# Arduino-Mini-v5.net
KiCad netlist of a schematic drawn in EAGLE
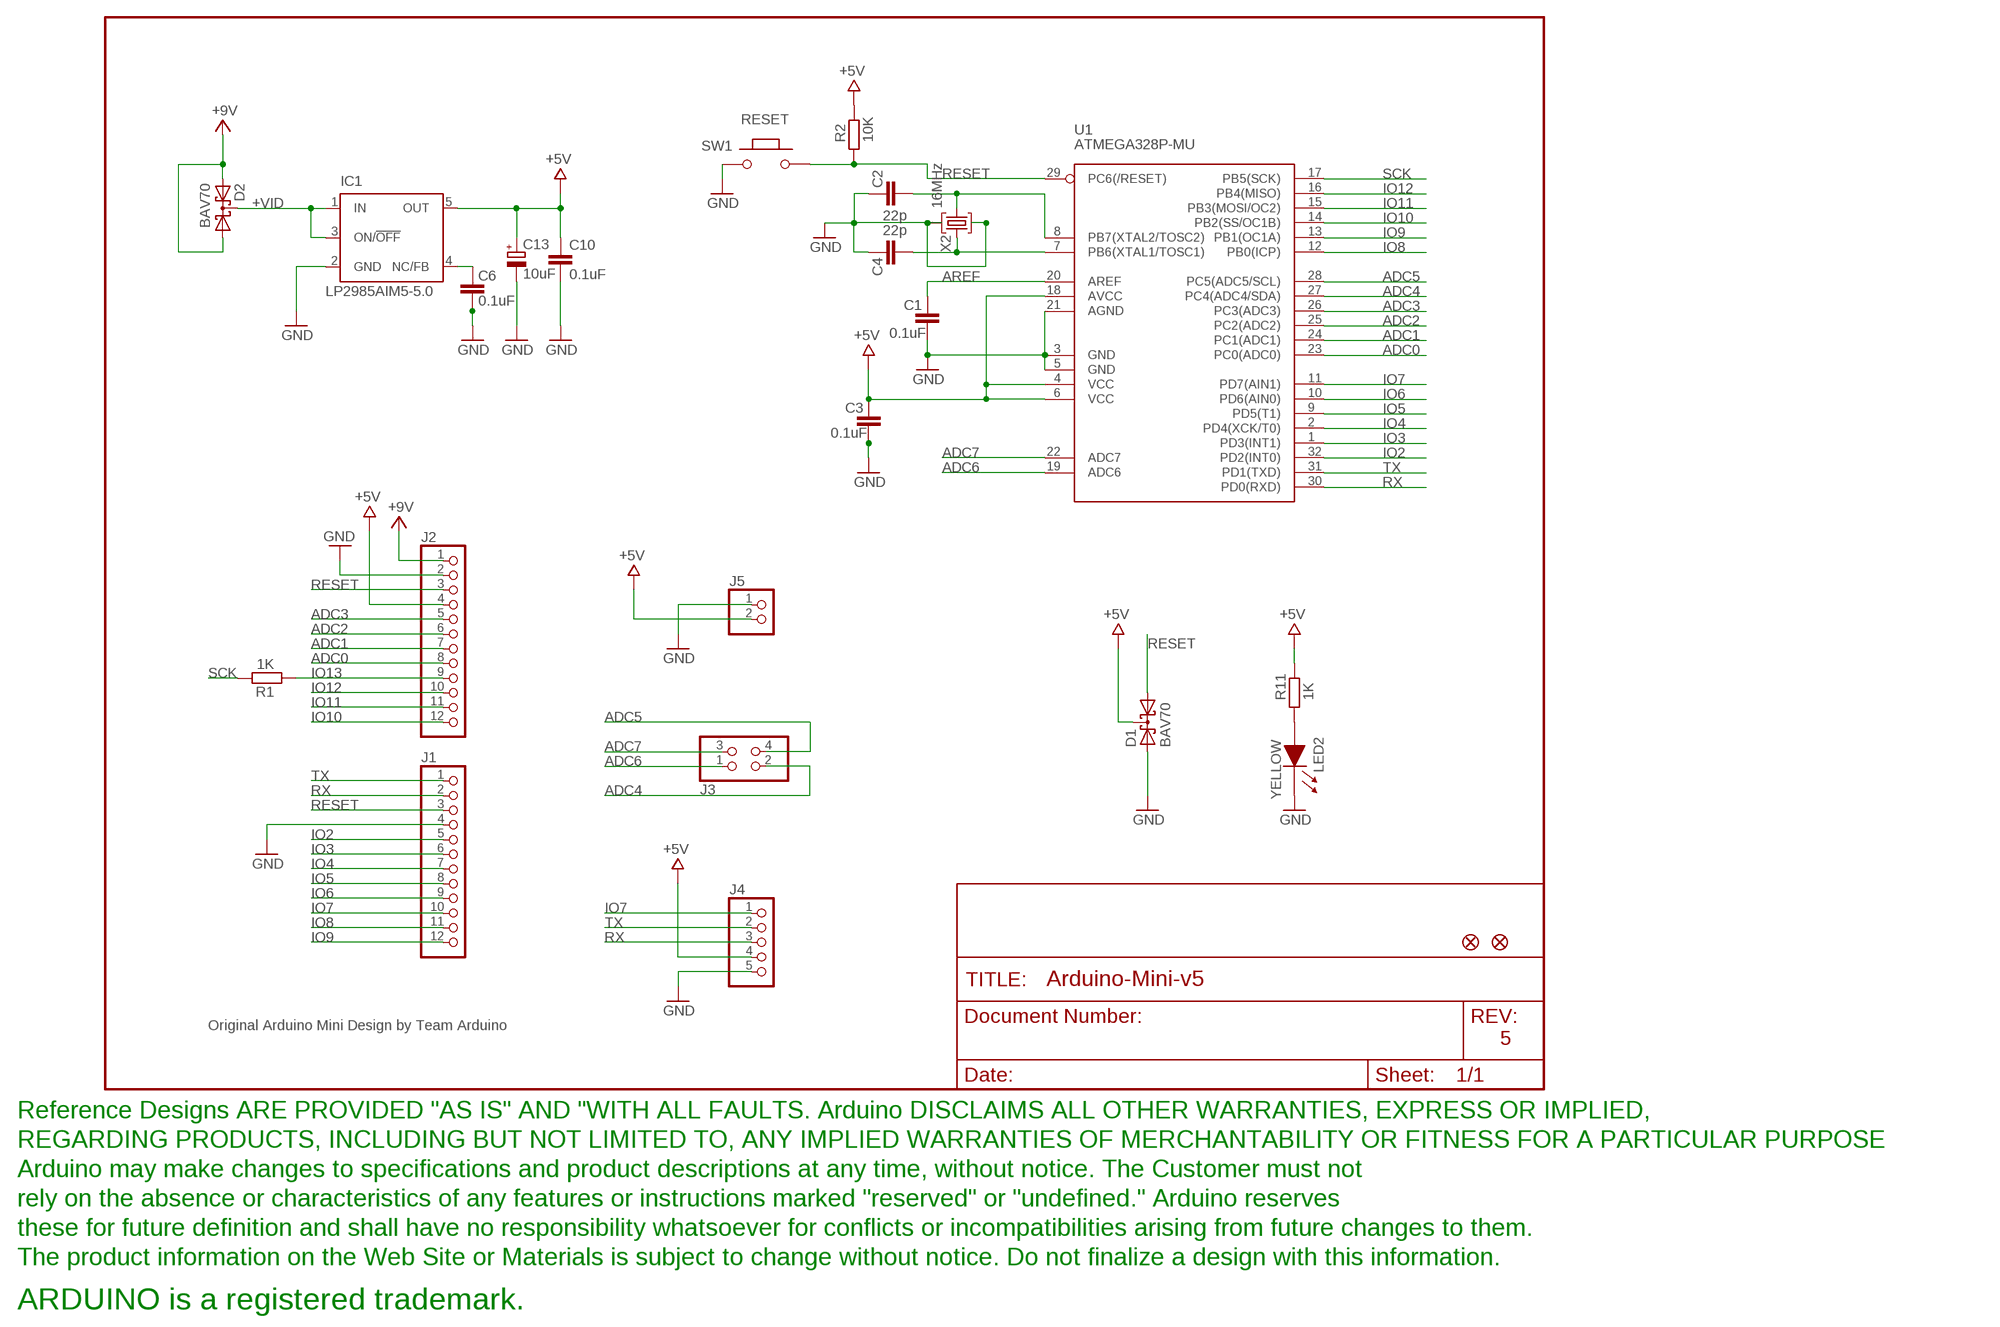
[diagram p0: schematic, sheet 1]

(export (version "E")
  (design (tool "Eeschema 10.0.6"))
  (components
    (comp (ref "C1")
      (value "0.1uF")
      (footprint "eagle-import:C0603-ROUND")
      (libsource (lib "eagle-import") (part "C-EUC0603"))
    )
    (comp (ref "C2")
      (value "22p")
      (footprint "eagle-import:C0603-ROUND")
      (libsource (lib "eagle-import") (part "C-EUC0603"))
    )
    (comp (ref "C3")
      (value "0.1uF")
      (footprint "eagle-import:C0603-ROUND")
      (libsource (lib "eagle-import") (part "C-EUC0603"))
    )
    (comp (ref "C4")
      (value "22p")
      (footprint "eagle-import:C0603-ROUND")
      (libsource (lib "eagle-import") (part "C-EUC0603"))
    )
    (comp (ref "C6")
      (value "0.1uF")
      (footprint "eagle-import:C0603-ROUND")
      (libsource (lib "eagle-import") (part "C-EUC0603"))
    )
    (comp (ref "C10")
      (value "0.1uF")
      (footprint "eagle-import:C0603-ROUND")
      (libsource (lib "eagle-import") (part "C-EUC0603"))
    )
    (comp (ref "C13")
      (value "10uF")
      (footprint "eagle-import:SMC_B")
      (libsource (lib "eagle-import") (part "CPOL-EUSMCB"))
    )
    (comp (ref "D1")
      (value "BAV70")
      (footprint "eagle-import:SOT23")
      (libsource (lib "eagle-import") (part "BAS70-05"))
    )
    (comp (ref "D2")
      (value "BAV70")
      (footprint "eagle-import:SOT23")
      (libsource (lib "eagle-import") (part "BAS70-05"))
    )
    (comp (ref "IC1")
      (value "LP2985AIM5-5.0")
      (footprint "eagle-import:SOT23-DBV")
      (libsource (lib "eagle-import") (part "LP2985-XXDBVR50"))
    )
    (comp (ref "J1")
      (value "PINHD-1X12")
      (footprint "eagle-import:1X12")
      (libsource (lib "eagle-import") (part "PINHD-1X12"))
    )
    (comp (ref "J2")
      (value "PINHD-1X12")
      (footprint "eagle-import:1X12")
      (libsource (lib "eagle-import") (part "PINHD-1X12"))
    )
    (comp (ref "J3")
      (value "PINHD-2X2")
      (footprint "eagle-import:2X02")
      (libsource (lib "eagle-import") (part "PINHD-2X2"))
    )
    (comp (ref "J4")
      (value "PINHD-1X5")
      (footprint "eagle-import:1X5")
      (libsource (lib "eagle-import") (part "PINHD-1X5"))
    )
    (comp (ref "J5")
      (value "PINHD-1X2")
      (footprint "eagle-import:1X2")
      (libsource (lib "eagle-import") (part "PINHD-1X2"))
    )
    (comp (ref "LED2")
      (value "YELLOW")
      (footprint "eagle-import:SMD_LED0805")
      (libsource (lib "eagle-import") (part "MYSMD_LED0805"))
    )
    (comp (ref "R1")
      (value "1K")
      (footprint "eagle-import:R0603-ROUND")
      (libsource (lib "eagle-import") (part "R-EU_R0603"))
    )
    (comp (ref "R2")
      (value "10K")
      (footprint "eagle-import:R0603-ROUND")
      (libsource (lib "eagle-import") (part "R-EU_R0603"))
    )
    (comp (ref "R11")
      (value "1K")
      (footprint "eagle-import:R0603-ROUND")
      (libsource (lib "eagle-import") (part "R-EU_R0603"))
    )
    (comp (ref "SW1")
      (value "RESET")
      (footprint "eagle-import:SMD_157SW")
      (libsource (lib "eagle-import") (part "MYSMD_PB157"))
    )
    (comp (ref "U$2")
      (value "FIDUCIAL1X2")
      (footprint "eagle-import:FIDUCIAL-1X2")
      (libsource (lib "eagle-import") (part "FIDUCIAL1X2"))
    )
    (comp (ref "U$4")
      (value "FIDUCIAL1X2")
      (footprint "eagle-import:FIDUCIAL-1X2")
      (libsource (lib "eagle-import") (part "FIDUCIAL1X2"))
    )
    (comp (ref "U$11")
      (value "DISCLAIMER")
      (footprint "eagle-import:DISCLAIMER")
      (libsource (lib "eagle-import") (part "DISCLAIMER"))
    )
    (comp (ref "U1")
      (value "ATMEGA328P-MU")
      (footprint "eagle-import:MLF32-M1-A")
      (libsource (lib "eagle-import") (part "ATMEGAXX8-MU"))
    )
    (comp (ref "X2")
      (value "16MHz")
      (footprint "eagle-import:CRYSTAL-3.2-2.5")
      (libsource (lib "eagle-import") (part "CRYSTAL-3.2-2.5"))
    )
  )
  (nets
    (net (code "1") (name "+5V") (class "Default")
      (node (ref "C10") (pin "1") (pinfunction "1_1") (pintype "passive"))
      (node (ref "C13") (pin "+") (pinfunction "+_+") (pintype "passive"))
      (node (ref "C3") (pin "2") (pinfunction "2_2") (pintype "passive"))
      (node (ref "D1") (pin "3") (pinfunction "C_3") (pintype "passive"))
      (node (ref "IC1") (pin "5") (pinfunction "OUT_5") (pintype "passive"))
      (node (ref "J2") (pin "4") (pinfunction "4_4") (pintype "passive"))
      (node (ref "J4") (pin "4") (pinfunction "4_4") (pintype "passive"))
      (node (ref "J5") (pin "2") (pinfunction "2_2") (pintype "passive"))
      (node (ref "R11") (pin "2") (pinfunction "2_2") (pintype "passive"))
      (node (ref "R2") (pin "2") (pinfunction "2_2") (pintype "passive"))
      (node (ref "U1") (pin "18") (pinfunction "AVCC_18") (pintype "bidirectional"))
      (node (ref "U1") (pin "4") (pinfunction "VCC_4") (pintype "bidirectional"))
      (node (ref "U1") (pin "6") (pinfunction "VCC_6") (pintype "bidirectional"))
    )
    (net (code "2") (name "+9V") (class "Default")
      (node (ref "D2") (pin "1") (pinfunction "A1_1") (pintype "passive"))
      (node (ref "D2") (pin "2") (pinfunction "A2_2") (pintype "passive"))
      (node (ref "J2") (pin "1") (pinfunction "1_1") (pintype "passive"))
    )
    (net (code "3") (name "/+VID") (class "Default")
      (node (ref "D2") (pin "3") (pinfunction "C_3") (pintype "passive"))
      (node (ref "IC1") (pin "1") (pinfunction "IN_1") (pintype "input"))
      (node (ref "IC1") (pin "3") (pinfunction "ON/~{OFF}_3") (pintype "input"))
    )
    (net (code "4") (name "/ADC0") (class "Default")
      (node (ref "J2") (pin "8") (pinfunction "8_8") (pintype "passive"))
      (node (ref "U1") (pin "23") (pinfunction "PC0(ADC0)_23") (pintype "bidirectional"))
    )
    (net (code "5") (name "/ADC1") (class "Default")
      (node (ref "J2") (pin "7") (pinfunction "7_7") (pintype "passive"))
      (node (ref "U1") (pin "24") (pinfunction "PC1(ADC1)_24") (pintype "bidirectional"))
    )
    (net (code "6") (name "/ADC2") (class "Default")
      (node (ref "J2") (pin "6") (pinfunction "6_6") (pintype "passive"))
      (node (ref "U1") (pin "25") (pinfunction "PC2(ADC2)_25") (pintype "bidirectional"))
    )
    (net (code "7") (name "/ADC3") (class "Default")
      (node (ref "J2") (pin "5") (pinfunction "5_5") (pintype "passive"))
      (node (ref "U1") (pin "26") (pinfunction "PC3(ADC3)_26") (pintype "bidirectional"))
    )
    (net (code "8") (name "/ADC4") (class "Default")
      (node (ref "J3") (pin "2") (pinfunction "2_2") (pintype "passive"))
      (node (ref "U1") (pin "27") (pinfunction "PC4(ADC4/SDA)_27") (pintype "bidirectional"))
    )
    (net (code "9") (name "/ADC5") (class "Default")
      (node (ref "J3") (pin "4") (pinfunction "4_4") (pintype "passive"))
      (node (ref "U1") (pin "28") (pinfunction "PC5(ADC5/SCL)_28") (pintype "bidirectional"))
    )
    (net (code "10") (name "/ADC6") (class "Default")
      (node (ref "J3") (pin "1") (pinfunction "1_1") (pintype "passive"))
      (node (ref "U1") (pin "19") (pinfunction "ADC6_19") (pintype "bidirectional"))
    )
    (net (code "11") (name "/ADC7") (class "Default")
      (node (ref "J3") (pin "3") (pinfunction "3_3") (pintype "passive"))
      (node (ref "U1") (pin "22") (pinfunction "ADC7_22") (pintype "bidirectional"))
    )
    (net (code "12") (name "/AREF") (class "Default")
      (node (ref "C1") (pin "2") (pinfunction "2_2") (pintype "passive"))
      (node (ref "U1") (pin "20") (pinfunction "AREF_20") (pintype "bidirectional"))
    )
    (net (code "13") (name "/IO2") (class "Default")
      (node (ref "J1") (pin "5") (pinfunction "5_5") (pintype "passive"))
      (node (ref "U1") (pin "32") (pinfunction "PD2(INT0)_32") (pintype "bidirectional"))
    )
    (net (code "14") (name "/IO3") (class "Default")
      (node (ref "J1") (pin "6") (pinfunction "6_6") (pintype "passive"))
      (node (ref "U1") (pin "1") (pinfunction "PD3(INT1)_1") (pintype "bidirectional"))
    )
    (net (code "15") (name "/IO4") (class "Default")
      (node (ref "J1") (pin "7") (pinfunction "7_7") (pintype "passive"))
      (node (ref "U1") (pin "2") (pinfunction "PD4(XCK/T0)_2") (pintype "bidirectional"))
    )
    (net (code "16") (name "/IO5") (class "Default")
      (node (ref "J1") (pin "8") (pinfunction "8_8") (pintype "passive"))
      (node (ref "U1") (pin "9") (pinfunction "PD5(T1)_9") (pintype "bidirectional"))
    )
    (net (code "17") (name "/IO6") (class "Default")
      (node (ref "J1") (pin "9") (pinfunction "9_9") (pintype "passive"))
      (node (ref "U1") (pin "10") (pinfunction "PD6(AIN0)_10") (pintype "bidirectional"))
    )
    (net (code "18") (name "/IO7") (class "Default")
      (node (ref "J1") (pin "10") (pinfunction "10_10") (pintype "passive"))
      (node (ref "J4") (pin "1") (pinfunction "1_1") (pintype "passive"))
      (node (ref "U1") (pin "11") (pinfunction "PD7(AIN1)_11") (pintype "bidirectional"))
    )
    (net (code "19") (name "/IO8") (class "Default")
      (node (ref "J1") (pin "11") (pinfunction "11_11") (pintype "passive"))
      (node (ref "U1") (pin "12") (pinfunction "PB0(ICP)_12") (pintype "bidirectional"))
    )
    (net (code "20") (name "/IO9") (class "Default")
      (node (ref "J1") (pin "12") (pinfunction "12_12") (pintype "passive"))
      (node (ref "U1") (pin "13") (pinfunction "PB1(OC1A)_13") (pintype "bidirectional"))
    )
    (net (code "21") (name "/IO10") (class "Default")
      (node (ref "J2") (pin "12") (pinfunction "12_12") (pintype "passive"))
      (node (ref "U1") (pin "14") (pinfunction "PB2(SS/OC1B)_14") (pintype "bidirectional"))
    )
    (net (code "22") (name "/IO11") (class "Default")
      (node (ref "J2") (pin "11") (pinfunction "11_11") (pintype "passive"))
      (node (ref "U1") (pin "15") (pinfunction "PB3(MOSI/OC2)_15") (pintype "bidirectional"))
    )
    (net (code "23") (name "/IO12") (class "Default")
      (node (ref "J2") (pin "10") (pinfunction "10_10") (pintype "passive"))
      (node (ref "U1") (pin "16") (pinfunction "PB4(MISO)_16") (pintype "bidirectional"))
    )
    (net (code "24") (name "/IO13") (class "Default")
      (node (ref "J2") (pin "9") (pinfunction "9_9") (pintype "passive"))
      (node (ref "R1") (pin "1") (pinfunction "1_1") (pintype "passive"))
    )
    (net (code "25") (name "/RESET") (class "Default")
      (node (ref "D1") (pin "2") (pinfunction "A2_2") (pintype "passive"))
      (node (ref "J1") (pin "3") (pinfunction "3_3") (pintype "passive"))
      (node (ref "J2") (pin "3") (pinfunction "3_3") (pintype "passive"))
      (node (ref "R2") (pin "1") (pinfunction "1_1") (pintype "passive"))
      (node (ref "SW1") (pin "2") (pinfunction "2_2") (pintype "passive"))
      (node (ref "U1") (pin "29") (pinfunction "PC6(/RESET)_29") (pintype "bidirectional"))
    )
    (net (code "26") (name "/RX") (class "Default")
      (node (ref "J1") (pin "2") (pinfunction "2_2") (pintype "passive"))
      (node (ref "J4") (pin "3") (pinfunction "3_3") (pintype "passive"))
      (node (ref "U1") (pin "30") (pinfunction "PD0(RXD)_30") (pintype "bidirectional"))
    )
    (net (code "27") (name "/SCK") (class "Default")
      (node (ref "R1") (pin "2") (pinfunction "2_2") (pintype "passive"))
      (node (ref "U1") (pin "17") (pinfunction "PB5(SCK)_17") (pintype "bidirectional"))
    )
    (net (code "28") (name "/TX") (class "Default")
      (node (ref "J1") (pin "1") (pinfunction "1_1") (pintype "passive"))
      (node (ref "J4") (pin "2") (pinfunction "2_2") (pintype "passive"))
      (node (ref "U1") (pin "31") (pinfunction "PD1(TXD)_31") (pintype "bidirectional"))
    )
    (net (code "29") (name "GND") (class "Default")
      (node (ref "C1") (pin "1") (pinfunction "1_1") (pintype "passive"))
      (node (ref "C10") (pin "2") (pinfunction "2_2") (pintype "passive"))
      (node (ref "C13") (pin "-") (pinfunction "-_-") (pintype "passive"))
      (node (ref "C2") (pin "2") (pinfunction "2_2") (pintype "passive"))
      (node (ref "C3") (pin "1") (pinfunction "1_1") (pintype "passive"))
      (node (ref "C4") (pin "2") (pinfunction "2_2") (pintype "passive"))
      (node (ref "C6") (pin "1") (pinfunction "1_1") (pintype "passive"))
      (node (ref "D1") (pin "1") (pinfunction "A1_1") (pintype "passive"))
      (node (ref "IC1") (pin "2") (pinfunction "GND_2") (pintype "power_in"))
      (node (ref "J1") (pin "4") (pinfunction "4_4") (pintype "passive"))
      (node (ref "J2") (pin "2") (pinfunction "2_2") (pintype "passive"))
      (node (ref "J4") (pin "5") (pinfunction "5_5") (pintype "passive"))
      (node (ref "J5") (pin "1") (pinfunction "1_1") (pintype "passive"))
      (node (ref "LED2") (pin "1") (pinfunction "CA_1") (pintype "passive"))
      (node (ref "SW1") (pin "1") (pinfunction "1_1") (pintype "passive"))
      (node (ref "U1") (pin "21") (pinfunction "AGND_21") (pintype "bidirectional"))
      (node (ref "U1") (pin "3") (pinfunction "GND_3") (pintype "bidirectional"))
      (node (ref "U1") (pin "5") (pinfunction "GND_5") (pintype "bidirectional"))
      (node (ref "X2") (pin "2") (pinfunction "GND_2") (pintype "passive"))
      (node (ref "X2") (pin "4") (pinfunction "GND_4") (pintype "passive"))
    )
    (net (code "30") (name "Net-(IC1-NC{slash}FB)") (class "Default")
      (node (ref "C6") (pin "2") (pinfunction "2_2") (pintype "passive"))
      (node (ref "IC1") (pin "4") (pinfunction "NC/FB_4") (pintype "passive"))
    )
    (net (code "31") (name "Net-(LED2-AN)") (class "Default")
      (node (ref "LED2") (pin "2") (pinfunction "AN_2") (pintype "passive"))
      (node (ref "R11") (pin "1") (pinfunction "1_1") (pintype "passive"))
    )
    (net (code "32") (name "Net-(U1-PB6(XTAL1{slash}TOSC1))") (class "Default")
      (node (ref "C4") (pin "1") (pinfunction "1_1") (pintype "passive"))
      (node (ref "U1") (pin "7") (pinfunction "PB6(XTAL1/TOSC1)_7") (pintype "bidirectional"))
      (node (ref "X2") (pin "1") (pinfunction "C1_1") (pintype "passive"))
    )
    (net (code "33") (name "Net-(U1-PB7(XTAL2{slash}TOSC2))") (class "Default")
      (node (ref "C2") (pin "1") (pinfunction "1_1") (pintype "passive"))
      (node (ref "U1") (pin "8") (pinfunction "PB7(XTAL2/TOSC2)_8") (pintype "bidirectional"))
      (node (ref "X2") (pin "3") (pinfunction "C2_3") (pintype "passive"))
    )
  )
)
